# SCH_Esp32-Dev-board_2026-06-18.net
KiCad netlist of a schematic drawn in EasyEDA
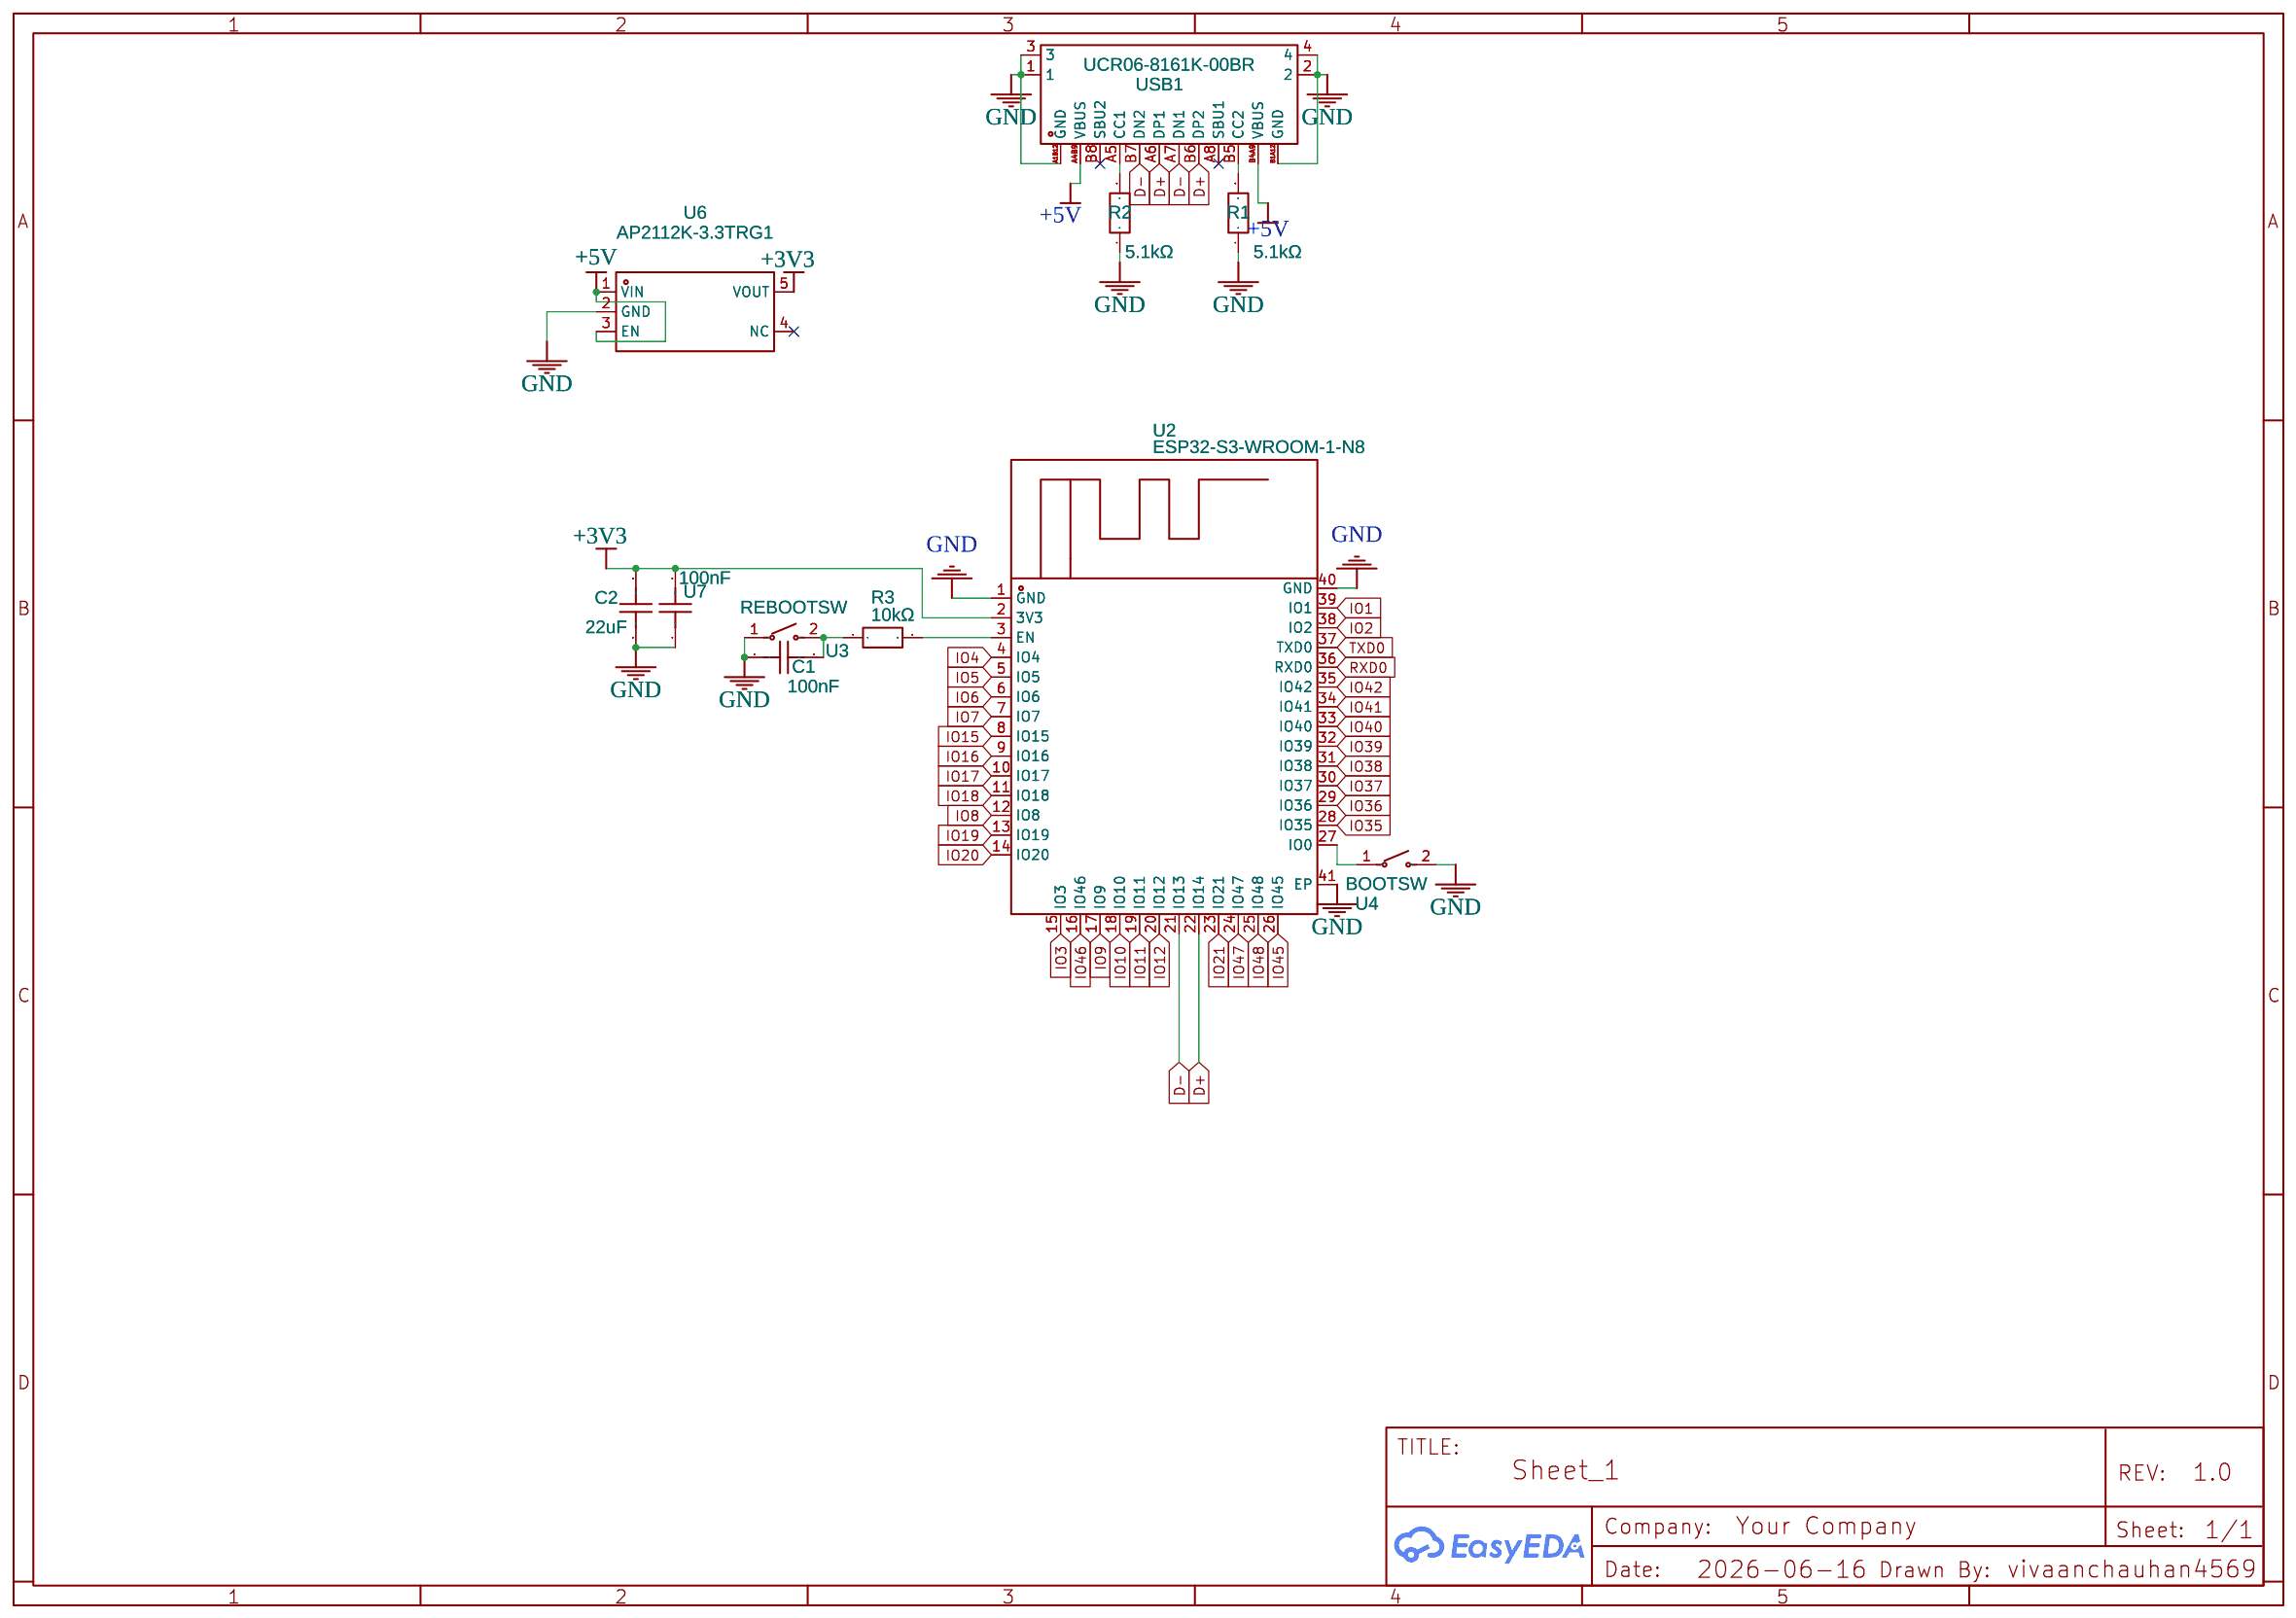
[diagram p0: schematic sheet]

(export (version "E")
  (design (tool "Eeschema 10.0.6"))
  (components
    (comp (ref "C1")
      (value "100nF")
      (fields (field (name "Manufacturer Part") "C0201X7R100-104KNP") (field (name "Manufacturer") "Venkel"))
      (libsource (lib "") (part "C0201X7R100-104KNP"))
    )
    (comp (ref "C2")
      (value "22uF")
      (fields
        (field (name "Manufacturer Part") "CGA0603X5R226M6R3JT")
        (field (name "Manufacturer") "HRE(芯声)")
      )
      (libsource (lib "") (part "CGA0603X5R226M6R3JT"))
    )
    (comp (ref "R1")
      (value "5.1kΩ")
      (fields
        (field (name "Manufacturer Part") "HQ02WAF5101TCE")
        (field (name "Manufacturer") "UNI-ROYAL(厚声)")
      )
      (libsource (lib "") (part "HQ02WAF5101TCE"))
    )
    (comp (ref "R2")
      (value "5.1kΩ")
      (fields
        (field (name "Manufacturer Part") "HQ02WAF5101TCE")
        (field (name "Manufacturer") "UNI-ROYAL(厚声)")
      )
      (libsource (lib "") (part "HQ02WAF5101TCE"))
    )
    (comp (ref "R3")
      (value "10kΩ")
      (fields
        (field (name "Manufacturer Part") "CPF0603B10KE1")
        (field (name "Manufacturer") "TE Connectivity(泰科电子)")
      )
      (libsource (lib "") (part "CPF0603B10KE1"))
    )
    (comp (ref "U2")
      (value "ESP32-S3-WROOM-1-N8")
      (fields (field (name "Manufacturer") "ESPRESSIF(乐鑫)"))
      (libsource (lib "") (part "ESP32-S3-WROOM-1-N8"))
    )
    (comp (ref "U3")
      (value "REBOOTSW")
      (fields (field (name "Manufacturer Part") "SW-PB"))
      (libsource (lib "") (part "SW-PB_C9900011101"))
    )
    (comp (ref "U4")
      (value "BOOTSW")
      (fields (field (name "Manufacturer Part") "SW-PB"))
      (libsource (lib "") (part "SW-PB_C9900011101"))
    )
    (comp (ref "U6")
      (value "AP2112K-3.3TRG1")
      (fields (field (name "Manufacturer") "DIODES(美台)"))
      (libsource (lib "") (part "AP2112K-3.3TRG1"))
    )
    (comp (ref "U7")
      (value "100nF")
      (fields (field (name "Manufacturer Part") "AM03B104K500AT") (field (name "Manufacturer") "FH(风华)"))
      (libsource (lib "") (part "AM03B104K500AT"))
    )
    (comp (ref "USB1") (value "UCR06-8161K-00BR") (libsource (lib "") (part "UCR06-8161K-00BR")))
  )
  (nets
    (net (code "1") (name "+3V3") (class "Default")
      (node (ref "C2") (pin "2") (pinfunction "2_2") (pintype "unspecified"))
      (node (ref "U2") (pin "2") (pinfunction "3V3_2") (pintype "unspecified"))
      (node (ref "U6") (pin "5") (pinfunction "VOUT_5") (pintype "unspecified"))
      (node (ref "U7") (pin "2") (pinfunction "2_2") (pintype "unspecified"))
    )
    (net (code "2") (name "+5V") (class "Default")
      (node (ref "U6") (pin "1") (pinfunction "VIN_1") (pintype "unspecified"))
      (node (ref "U6") (pin "3") (pinfunction "EN_3") (pintype "unspecified"))
      (node (ref "USB1") (pin "A4B9") (pinfunction "VBUS_A4B9") (pintype "unspecified"))
      (node (ref "USB1") (pin "B4A9") (pinfunction "VBUS_B4A9") (pintype "unspecified"))
    )
    (net (code "3") (name "D+") (class "Default")
      (node (ref "U2") (pin "22") (pinfunction "IO14_22") (pintype "unspecified"))
      (node (ref "USB1") (pin "A6") (pinfunction "DP1_A6") (pintype "unspecified"))
      (node (ref "USB1") (pin "B6") (pinfunction "DP2_B6") (pintype "unspecified"))
    )
    (net (code "4") (name "D-") (class "Default")
      (node (ref "U2") (pin "21") (pinfunction "IO13_21") (pintype "unspecified"))
      (node (ref "USB1") (pin "A7") (pinfunction "DN1_A7") (pintype "unspecified"))
      (node (ref "USB1") (pin "B7") (pinfunction "DN2_B7") (pintype "unspecified"))
    )
    (net (code "5") (name "GND") (class "Default")
      (node (ref "C1") (pin "1") (pinfunction "1_1") (pintype "unspecified"))
      (node (ref "C2") (pin "1") (pinfunction "1_1") (pintype "unspecified"))
      (node (ref "R1") (pin "1") (pinfunction "1_1") (pintype "unspecified"))
      (node (ref "R2") (pin "1") (pinfunction "1_1") (pintype "unspecified"))
      (node (ref "U2") (pin "1") (pinfunction "GND_1") (pintype "unspecified"))
      (node (ref "U2") (pin "40") (pinfunction "GND_40") (pintype "unspecified"))
      (node (ref "U2") (pin "41") (pinfunction "EP_41") (pintype "unspecified"))
      (node (ref "U3") (pin "1") (pinfunction "1_1") (pintype "unspecified"))
      (node (ref "U4") (pin "2") (pinfunction "2_2") (pintype "unspecified"))
      (node (ref "U6") (pin "2") (pinfunction "GND_2") (pintype "unspecified"))
      (node (ref "U7") (pin "1") (pinfunction "1_1") (pintype "unspecified"))
      (node (ref "USB1") (pin "1") (pinfunction "1_1") (pintype "unspecified"))
      (node (ref "USB1") (pin "2") (pinfunction "2_2") (pintype "unspecified"))
      (node (ref "USB1") (pin "3") (pinfunction "3_3") (pintype "unspecified"))
      (node (ref "USB1") (pin "4") (pinfunction "4_4") (pintype "unspecified"))
      (node (ref "USB1") (pin "A1B12") (pinfunction "GND_A1B12") (pintype "unspecified"))
      (node (ref "USB1") (pin "B1A12") (pinfunction "GND_B1A12") (pintype "unspecified"))
    )
    (net (code "6") (name "IO1") (class "Default")
      (node (ref "U2") (pin "39") (pinfunction "IO1_39") (pintype "unspecified"))
    )
    (net (code "7") (name "IO2") (class "Default")
      (node (ref "U2") (pin "38") (pinfunction "IO2_38") (pintype "unspecified"))
    )
    (net (code "8") (name "IO3") (class "Default")
      (node (ref "U2") (pin "15") (pinfunction "IO3_15") (pintype "unspecified"))
    )
    (net (code "9") (name "IO4") (class "Default")
      (node (ref "U2") (pin "4") (pinfunction "IO4_4") (pintype "unspecified"))
    )
    (net (code "10") (name "IO5") (class "Default")
      (node (ref "U2") (pin "5") (pinfunction "IO5_5") (pintype "unspecified"))
    )
    (net (code "11") (name "IO6") (class "Default")
      (node (ref "U2") (pin "6") (pinfunction "IO6_6") (pintype "unspecified"))
    )
    (net (code "12") (name "IO7") (class "Default")
      (node (ref "U2") (pin "7") (pinfunction "IO7_7") (pintype "unspecified"))
    )
    (net (code "13") (name "IO8") (class "Default")
      (node (ref "U2") (pin "12") (pinfunction "IO8_12") (pintype "unspecified"))
    )
    (net (code "14") (name "IO9") (class "Default")
      (node (ref "U2") (pin "17") (pinfunction "IO9_17") (pintype "unspecified"))
    )
    (net (code "15") (name "IO10") (class "Default")
      (node (ref "U2") (pin "18") (pinfunction "IO10_18") (pintype "unspecified"))
    )
    (net (code "16") (name "IO11") (class "Default")
      (node (ref "U2") (pin "19") (pinfunction "IO11_19") (pintype "unspecified"))
    )
    (net (code "17") (name "IO12") (class "Default")
      (node (ref "U2") (pin "20") (pinfunction "IO12_20") (pintype "unspecified"))
    )
    (net (code "18") (name "IO15") (class "Default")
      (node (ref "U2") (pin "8") (pinfunction "IO15_8") (pintype "unspecified"))
    )
    (net (code "19") (name "IO16") (class "Default")
      (node (ref "U2") (pin "9") (pinfunction "IO16_9") (pintype "unspecified"))
    )
    (net (code "20") (name "IO17") (class "Default")
      (node (ref "U2") (pin "10") (pinfunction "IO17_10") (pintype "unspecified"))
    )
    (net (code "21") (name "IO18") (class "Default")
      (node (ref "U2") (pin "11") (pinfunction "IO18_11") (pintype "unspecified"))
    )
    (net (code "22") (name "IO19") (class "Default")
      (node (ref "U2") (pin "13") (pinfunction "IO19_13") (pintype "unspecified"))
    )
    (net (code "23") (name "IO20") (class "Default")
      (node (ref "U2") (pin "14") (pinfunction "IO20_14") (pintype "unspecified"))
    )
    (net (code "24") (name "IO21") (class "Default")
      (node (ref "U2") (pin "23") (pinfunction "IO21_23") (pintype "unspecified"))
    )
    (net (code "25") (name "IO35") (class "Default")
      (node (ref "U2") (pin "28") (pinfunction "IO35_28") (pintype "unspecified"))
    )
    (net (code "26") (name "IO36") (class "Default")
      (node (ref "U2") (pin "29") (pinfunction "IO36_29") (pintype "unspecified"))
    )
    (net (code "27") (name "IO37") (class "Default")
      (node (ref "U2") (pin "30") (pinfunction "IO37_30") (pintype "unspecified"))
    )
    (net (code "28") (name "IO38") (class "Default")
      (node (ref "U2") (pin "31") (pinfunction "IO38_31") (pintype "unspecified"))
    )
    (net (code "29") (name "IO39") (class "Default")
      (node (ref "U2") (pin "32") (pinfunction "IO39_32") (pintype "unspecified"))
    )
    (net (code "30") (name "IO40") (class "Default")
      (node (ref "U2") (pin "33") (pinfunction "IO40_33") (pintype "unspecified"))
    )
    (net (code "31") (name "IO41") (class "Default")
      (node (ref "U2") (pin "34") (pinfunction "IO41_34") (pintype "unspecified"))
    )
    (net (code "32") (name "IO42") (class "Default")
      (node (ref "U2") (pin "35") (pinfunction "IO42_35") (pintype "unspecified"))
    )
    (net (code "33") (name "IO45") (class "Default")
      (node (ref "U2") (pin "26") (pinfunction "IO45_26") (pintype "unspecified"))
    )
    (net (code "34") (name "IO46") (class "Default")
      (node (ref "U2") (pin "16") (pinfunction "IO46_16") (pintype "unspecified"))
    )
    (net (code "35") (name "IO47") (class "Default")
      (node (ref "U2") (pin "24") (pinfunction "IO47_24") (pintype "unspecified"))
    )
    (net (code "36") (name "IO48") (class "Default")
      (node (ref "U2") (pin "25") (pinfunction "IO48_25") (pintype "unspecified"))
    )
    (net (code "37") (name "Net-(C1-Pad2)") (class "Default")
      (node (ref "C1") (pin "2") (pinfunction "2_2") (pintype "unspecified"))
      (node (ref "R3") (pin "1") (pinfunction "1_1") (pintype "unspecified"))
      (node (ref "U3") (pin "2") (pinfunction "2_2") (pintype "unspecified"))
    )
    (net (code "38") (name "Net-(U2-EN)") (class "Default")
      (node (ref "R3") (pin "2") (pinfunction "2_2") (pintype "unspecified"))
      (node (ref "U2") (pin "3") (pinfunction "EN_3") (pintype "unspecified"))
    )
    (net (code "39") (name "Net-(U2-IO0)") (class "Default")
      (node (ref "U2") (pin "27") (pinfunction "IO0_27") (pintype "unspecified"))
      (node (ref "U4") (pin "1") (pinfunction "1_1") (pintype "unspecified"))
    )
    (net (code "40") (name "Net-(USB1-CC1)") (class "Default")
      (node (ref "R2") (pin "2") (pinfunction "2_2") (pintype "unspecified"))
      (node (ref "USB1") (pin "A5") (pinfunction "CC1_A5") (pintype "unspecified"))
    )
    (net (code "41") (name "Net-(USB1-CC2)") (class "Default")
      (node (ref "R1") (pin "2") (pinfunction "2_2") (pintype "unspecified"))
      (node (ref "USB1") (pin "B5") (pinfunction "CC2_B5") (pintype "unspecified"))
    )
    (net (code "42") (name "RXD0") (class "Default")
      (node (ref "U2") (pin "36") (pinfunction "RXD0_36") (pintype "unspecified"))
    )
    (net (code "43") (name "TXD0") (class "Default")
      (node (ref "U2") (pin "37") (pinfunction "TXD0_37") (pintype "unspecified"))
    )
    (net (code "44") (name "unconnected-(U6-NC-Pad4)") (class "Default")
      (node (ref "U6") (pin "4") (pinfunction "NC_4") (pintype "unspecified+no_connect"))
    )
    (net (code "45") (name "unconnected-(USB1-SBU1-PadA8)") (class "Default")
      (node (ref "USB1") (pin "A8") (pinfunction "SBU1_A8") (pintype "unspecified+no_connect"))
    )
    (net (code "46") (name "unconnected-(USB1-SBU2-PadB8)") (class "Default")
      (node (ref "USB1") (pin "B8") (pinfunction "SBU2_B8") (pintype "unspecified+no_connect"))
    )
  )
)
